# FPGA2_PWR.net
KiCad netlist of a schematic drawn in Altium Designer
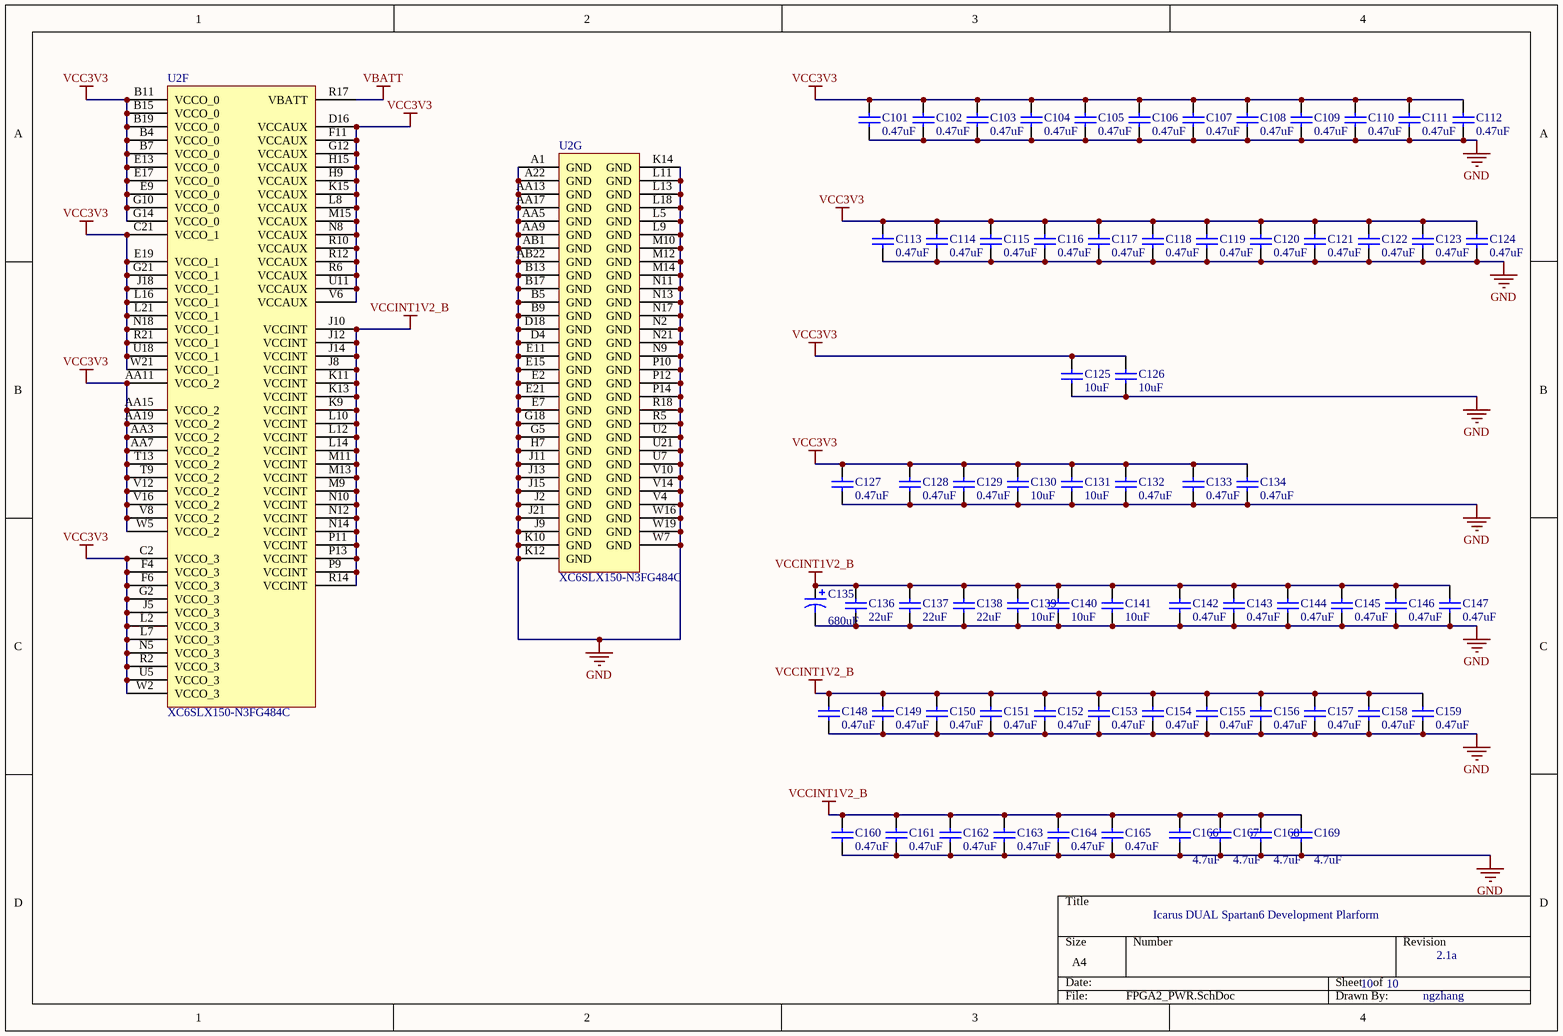
[diagram p0: FPGA2_PWR.SchDoc]

(export (version "E")
  (design (tool "Eeschema 10.0.6"))
  (components
    (comp (ref "C101")
      (value "0.47uF")
      (footprint "BGA0402")
      (description "Capacitor (Semiconductor SIM Model)")
      (fields (field (name "PUBLISHER") "Altium Limited"))
      (libsource (lib "Miscellaneous Devices") (part "Cap Semi"))
    )
    (comp (ref "C102")
      (value "0.47uF")
      (footprint "BGA0402")
      (description "Capacitor (Semiconductor SIM Model)")
      (fields (field (name "PUBLISHER") "Altium Limited"))
      (libsource (lib "Miscellaneous Devices") (part "Cap Semi"))
    )
    (comp (ref "C103")
      (value "0.47uF")
      (footprint "BGA0402")
      (description "Capacitor (Semiconductor SIM Model)")
      (fields (field (name "PUBLISHER") "Altium Limited"))
      (libsource (lib "Miscellaneous Devices") (part "Cap Semi"))
    )
    (comp (ref "C104")
      (value "0.47uF")
      (footprint "BGA0402")
      (description "Capacitor (Semiconductor SIM Model)")
      (fields (field (name "PUBLISHER") "Altium Limited"))
      (libsource (lib "Miscellaneous Devices") (part "Cap Semi"))
    )
    (comp (ref "C105")
      (value "0.47uF")
      (footprint "BGA0402")
      (description "Capacitor (Semiconductor SIM Model)")
      (fields (field (name "PUBLISHER") "Altium Limited"))
      (libsource (lib "Miscellaneous Devices") (part "Cap Semi"))
    )
    (comp (ref "C106")
      (value "0.47uF")
      (footprint "BGA0402")
      (description "Capacitor (Semiconductor SIM Model)")
      (fields (field (name "PUBLISHER") "Altium Limited"))
      (libsource (lib "Miscellaneous Devices") (part "Cap Semi"))
    )
    (comp (ref "C107")
      (value "0.47uF")
      (footprint "BGA0402")
      (description "Capacitor (Semiconductor SIM Model)")
      (fields (field (name "PUBLISHER") "Altium Limited"))
      (libsource (lib "Miscellaneous Devices") (part "Cap Semi"))
    )
    (comp (ref "C108")
      (value "0.47uF")
      (footprint "BGA0402")
      (description "Capacitor (Semiconductor SIM Model)")
      (fields (field (name "PUBLISHER") "Altium Limited"))
      (libsource (lib "Miscellaneous Devices") (part "Cap Semi"))
    )
    (comp (ref "C109")
      (value "0.47uF")
      (footprint "BGA0402")
      (description "Capacitor (Semiconductor SIM Model)")
      (fields (field (name "PUBLISHER") "Altium Limited"))
      (libsource (lib "Miscellaneous Devices") (part "Cap Semi"))
    )
    (comp (ref "C110")
      (value "0.47uF")
      (footprint "BGA0402")
      (description "Capacitor (Semiconductor SIM Model)")
      (fields (field (name "PUBLISHER") "Altium Limited"))
      (libsource (lib "Miscellaneous Devices") (part "Cap Semi"))
    )
    (comp (ref "C111")
      (value "0.47uF")
      (footprint "BGA0402")
      (description "Capacitor (Semiconductor SIM Model)")
      (fields (field (name "PUBLISHER") "Altium Limited"))
      (libsource (lib "Miscellaneous Devices") (part "Cap Semi"))
    )
    (comp (ref "C112")
      (value "0.47uF")
      (footprint "BGA0402")
      (description "Capacitor (Semiconductor SIM Model)")
      (fields (field (name "PUBLISHER") "Altium Limited"))
      (libsource (lib "Miscellaneous Devices") (part "Cap Semi"))
    )
    (comp (ref "C113")
      (value "0.47uF")
      (footprint "BGA0402")
      (description "Capacitor (Semiconductor SIM Model)")
      (fields (field (name "PUBLISHER") "Altium Limited"))
      (libsource (lib "Miscellaneous Devices") (part "Cap Semi"))
    )
    (comp (ref "C114")
      (value "0.47uF")
      (footprint "BGA0402")
      (description "Capacitor (Semiconductor SIM Model)")
      (fields (field (name "PUBLISHER") "Altium Limited"))
      (libsource (lib "Miscellaneous Devices") (part "Cap Semi"))
    )
    (comp (ref "C115")
      (value "0.47uF")
      (footprint "BGA0402")
      (description "Capacitor (Semiconductor SIM Model)")
      (fields (field (name "PUBLISHER") "Altium Limited"))
      (libsource (lib "Miscellaneous Devices") (part "Cap Semi"))
    )
    (comp (ref "C116")
      (value "0.47uF")
      (footprint "BGA0402")
      (description "Capacitor (Semiconductor SIM Model)")
      (fields (field (name "PUBLISHER") "Altium Limited"))
      (libsource (lib "Miscellaneous Devices") (part "Cap Semi"))
    )
    (comp (ref "C117")
      (value "0.47uF")
      (footprint "BGA0402")
      (description "Capacitor (Semiconductor SIM Model)")
      (fields (field (name "PUBLISHER") "Altium Limited"))
      (libsource (lib "Miscellaneous Devices") (part "Cap Semi"))
    )
    (comp (ref "C118")
      (value "0.47uF")
      (footprint "BGA0402")
      (description "Capacitor (Semiconductor SIM Model)")
      (fields (field (name "PUBLISHER") "Altium Limited"))
      (libsource (lib "Miscellaneous Devices") (part "Cap Semi"))
    )
    (comp (ref "C119")
      (value "0.47uF")
      (footprint "BGA0402")
      (description "Capacitor (Semiconductor SIM Model)")
      (fields (field (name "PUBLISHER") "Altium Limited"))
      (libsource (lib "Miscellaneous Devices") (part "Cap Semi"))
    )
    (comp (ref "C120")
      (value "0.47uF")
      (footprint "BGA0402")
      (description "Capacitor (Semiconductor SIM Model)")
      (fields (field (name "PUBLISHER") "Altium Limited"))
      (libsource (lib "Miscellaneous Devices") (part "Cap Semi"))
    )
    (comp (ref "C121")
      (value "0.47uF")
      (footprint "BGA0402")
      (description "Capacitor (Semiconductor SIM Model)")
      (fields (field (name "PUBLISHER") "Altium Limited"))
      (libsource (lib "Miscellaneous Devices") (part "Cap Semi"))
    )
    (comp (ref "C122")
      (value "0.47uF")
      (footprint "BGA0402")
      (description "Capacitor (Semiconductor SIM Model)")
      (fields (field (name "PUBLISHER") "Altium Limited"))
      (libsource (lib "Miscellaneous Devices") (part "Cap Semi"))
    )
    (comp (ref "C123")
      (value "0.47uF")
      (footprint "BGA0402")
      (description "Capacitor (Semiconductor SIM Model)")
      (fields (field (name "PUBLISHER") "Altium Limited"))
      (libsource (lib "Miscellaneous Devices") (part "Cap Semi"))
    )
    (comp (ref "C124")
      (value "0.47uF")
      (footprint "BGA0402")
      (description "Capacitor (Semiconductor SIM Model)")
      (fields (field (name "PUBLISHER") "Altium Limited"))
      (libsource (lib "Miscellaneous Devices") (part "Cap Semi"))
    )
    (comp (ref "C125")
      (value "10uF")
      (footprint "CAPC2012N")
      (description "Capacitor (Semiconductor SIM Model)")
      (fields (field (name "PUBLISHER") "Altium Limited"))
      (libsource (lib "Miscellaneous Devices") (part "Cap Semi"))
    )
    (comp (ref "C126")
      (value "10uF")
      (footprint "CAPC2012N")
      (description "Capacitor (Semiconductor SIM Model)")
      (fields (field (name "PUBLISHER") "Altium Limited"))
      (libsource (lib "Miscellaneous Devices") (part "Cap Semi"))
    )
    (comp (ref "C127")
      (value "0.47uF")
      (footprint "BGA0402")
      (description "Capacitor (Semiconductor SIM Model)")
      (fields (field (name "PUBLISHER") "Altium Limited"))
      (libsource (lib "Miscellaneous Devices") (part "Cap Semi"))
    )
    (comp (ref "C128")
      (value "0.47uF")
      (footprint "BGA0402")
      (description "Capacitor (Semiconductor SIM Model)")
      (fields (field (name "PUBLISHER") "Altium Limited"))
      (libsource (lib "Miscellaneous Devices") (part "Cap Semi"))
    )
    (comp (ref "C129")
      (value "0.47uF")
      (footprint "BGA0402")
      (description "Capacitor (Semiconductor SIM Model)")
      (fields (field (name "PUBLISHER") "Altium Limited"))
      (libsource (lib "Miscellaneous Devices") (part "Cap Semi"))
    )
    (comp (ref "C130")
      (value "10uF")
      (footprint "CAPC2012N")
      (description "Capacitor (Semiconductor SIM Model)")
      (fields (field (name "PUBLISHER") "Altium Limited"))
      (libsource (lib "Miscellaneous Devices") (part "Cap Semi"))
    )
    (comp (ref "C131")
      (value "10uF")
      (footprint "CAPC2012N")
      (description "Capacitor (Semiconductor SIM Model)")
      (fields (field (name "PUBLISHER") "Altium Limited"))
      (libsource (lib "Miscellaneous Devices") (part "Cap Semi"))
    )
    (comp (ref "C132")
      (value "0.47uF")
      (footprint "BGA0402")
      (description "Capacitor (Semiconductor SIM Model)")
      (fields (field (name "PUBLISHER") "Altium Limited"))
      (libsource (lib "Miscellaneous Devices") (part "Cap Semi"))
    )
    (comp (ref "C133")
      (value "0.47uF")
      (footprint "BGA0402")
      (description "Capacitor (Semiconductor SIM Model)")
      (fields (field (name "PUBLISHER") "Altium Limited"))
      (libsource (lib "Miscellaneous Devices") (part "Cap Semi"))
    )
    (comp (ref "C134")
      (value "0.47uF")
      (footprint "BGA0402")
      (description "Capacitor (Semiconductor SIM Model)")
      (fields (field (name "PUBLISHER") "Altium Limited"))
      (libsource (lib "Miscellaneous Devices") (part "Cap Semi"))
    )
    (comp (ref "C135")
      (value "680uF")
      (footprint "D")
      (description "Polarized Capacitor (Surface Mount)")
      (fields (field (name "PUBLISHER") "Altium Limited"))
      (libsource (lib "Miscellaneous Devices") (part "Cap Pol3"))
    )
    (comp (ref "C136")
      (value "22uF")
      (footprint "CAPC3216N")
      (description "Capacitor (Semiconductor SIM Model)")
      (fields (field (name "PUBLISHER") "Altium Limited"))
      (libsource (lib "Miscellaneous Devices") (part "Cap Semi"))
    )
    (comp (ref "C137")
      (value "22uF")
      (footprint "CAPC3216N")
      (description "Capacitor (Semiconductor SIM Model)")
      (fields (field (name "PUBLISHER") "Altium Limited"))
      (libsource (lib "Miscellaneous Devices") (part "Cap Semi"))
    )
    (comp (ref "C138")
      (value "22uF")
      (footprint "CAPC3216N")
      (description "Capacitor (Semiconductor SIM Model)")
      (fields (field (name "PUBLISHER") "Altium Limited"))
      (libsource (lib "Miscellaneous Devices") (part "Cap Semi"))
    )
    (comp (ref "C139")
      (value "10uF")
      (footprint "CAPC2012N")
      (description "Capacitor (Semiconductor SIM Model)")
      (fields (field (name "PUBLISHER") "Altium Limited"))
      (libsource (lib "Miscellaneous Devices") (part "Cap Semi"))
    )
    (comp (ref "C140")
      (value "10uF")
      (footprint "CAPC2012N")
      (description "Capacitor (Semiconductor SIM Model)")
      (fields (field (name "PUBLISHER") "Altium Limited"))
      (libsource (lib "Miscellaneous Devices") (part "Cap Semi"))
    )
    (comp (ref "C141")
      (value "10uF")
      (footprint "CAPC2012N")
      (description "Capacitor (Semiconductor SIM Model)")
      (fields (field (name "PUBLISHER") "Altium Limited"))
      (libsource (lib "Miscellaneous Devices") (part "Cap Semi"))
    )
    (comp (ref "C142")
      (value "0.47uF")
      (footprint "BGA0402")
      (description "Capacitor (Semiconductor SIM Model)")
      (fields (field (name "PUBLISHER") "Altium Limited"))
      (libsource (lib "Miscellaneous Devices") (part "Cap Semi"))
    )
    (comp (ref "C143")
      (value "0.47uF")
      (footprint "BGA0402")
      (description "Capacitor (Semiconductor SIM Model)")
      (fields (field (name "PUBLISHER") "Altium Limited"))
      (libsource (lib "Miscellaneous Devices") (part "Cap Semi"))
    )
    (comp (ref "C144")
      (value "0.47uF")
      (footprint "BGA0402")
      (description "Capacitor (Semiconductor SIM Model)")
      (fields (field (name "PUBLISHER") "Altium Limited"))
      (libsource (lib "Miscellaneous Devices") (part "Cap Semi"))
    )
    (comp (ref "C145")
      (value "0.47uF")
      (footprint "BGA0402")
      (description "Capacitor (Semiconductor SIM Model)")
      (fields (field (name "PUBLISHER") "Altium Limited"))
      (libsource (lib "Miscellaneous Devices") (part "Cap Semi"))
    )
    (comp (ref "C146")
      (value "0.47uF")
      (footprint "BGA0402")
      (description "Capacitor (Semiconductor SIM Model)")
      (fields (field (name "PUBLISHER") "Altium Limited"))
      (libsource (lib "Miscellaneous Devices") (part "Cap Semi"))
    )
    (comp (ref "C147")
      (value "0.47uF")
      (footprint "BGA0402")
      (description "Capacitor (Semiconductor SIM Model)")
      (fields (field (name "PUBLISHER") "Altium Limited"))
      (libsource (lib "Miscellaneous Devices") (part "Cap Semi"))
    )
    (comp (ref "C148")
      (value "0.47uF")
      (footprint "BGA0402")
      (description "Capacitor (Semiconductor SIM Model)")
      (fields (field (name "PUBLISHER") "Altium Limited"))
      (libsource (lib "Miscellaneous Devices") (part "Cap Semi"))
    )
    (comp (ref "C149")
      (value "0.47uF")
      (footprint "BGA0402")
      (description "Capacitor (Semiconductor SIM Model)")
      (fields (field (name "PUBLISHER") "Altium Limited"))
      (libsource (lib "Miscellaneous Devices") (part "Cap Semi"))
    )
    (comp (ref "C150")
      (value "0.47uF")
      (footprint "BGA0402")
      (description "Capacitor (Semiconductor SIM Model)")
      (fields (field (name "PUBLISHER") "Altium Limited"))
      (libsource (lib "Miscellaneous Devices") (part "Cap Semi"))
    )
    (comp (ref "C151")
      (value "0.47uF")
      (footprint "BGA0402")
      (description "Capacitor (Semiconductor SIM Model)")
      (fields (field (name "PUBLISHER") "Altium Limited"))
      (libsource (lib "Miscellaneous Devices") (part "Cap Semi"))
    )
    (comp (ref "C152")
      (value "0.47uF")
      (footprint "BGA0402")
      (description "Capacitor (Semiconductor SIM Model)")
      (fields (field (name "PUBLISHER") "Altium Limited"))
      (libsource (lib "Miscellaneous Devices") (part "Cap Semi"))
    )
    (comp (ref "C153")
      (value "0.47uF")
      (footprint "BGA0402")
      (description "Capacitor (Semiconductor SIM Model)")
      (fields (field (name "PUBLISHER") "Altium Limited"))
      (libsource (lib "Miscellaneous Devices") (part "Cap Semi"))
    )
    (comp (ref "C154")
      (value "0.47uF")
      (footprint "BGA0402")
      (description "Capacitor (Semiconductor SIM Model)")
      (fields (field (name "PUBLISHER") "Altium Limited"))
      (libsource (lib "Miscellaneous Devices") (part "Cap Semi"))
    )
    (comp (ref "C155")
      (value "0.47uF")
      (footprint "BGA0402")
      (description "Capacitor (Semiconductor SIM Model)")
      (fields (field (name "PUBLISHER") "Altium Limited"))
      (libsource (lib "Miscellaneous Devices") (part "Cap Semi"))
    )
    (comp (ref "C156")
      (value "0.47uF")
      (footprint "BGA0402")
      (description "Capacitor (Semiconductor SIM Model)")
      (fields (field (name "PUBLISHER") "Altium Limited"))
      (libsource (lib "Miscellaneous Devices") (part "Cap Semi"))
    )
    (comp (ref "C157")
      (value "0.47uF")
      (footprint "BGA0402")
      (description "Capacitor (Semiconductor SIM Model)")
      (fields (field (name "PUBLISHER") "Altium Limited"))
      (libsource (lib "Miscellaneous Devices") (part "Cap Semi"))
    )
    (comp (ref "C158")
      (value "0.47uF")
      (footprint "BGA0402")
      (description "Capacitor (Semiconductor SIM Model)")
      (fields (field (name "PUBLISHER") "Altium Limited"))
      (libsource (lib "Miscellaneous Devices") (part "Cap Semi"))
    )
    (comp (ref "C159")
      (value "0.47uF")
      (footprint "BGA0402")
      (description "Capacitor (Semiconductor SIM Model)")
      (fields (field (name "PUBLISHER") "Altium Limited"))
      (libsource (lib "Miscellaneous Devices") (part "Cap Semi"))
    )
    (comp (ref "C160")
      (value "0.47uF")
      (footprint "BGA0402")
      (description "Capacitor (Semiconductor SIM Model)")
      (fields (field (name "PUBLISHER") "Altium Limited"))
      (libsource (lib "Miscellaneous Devices") (part "Cap Semi"))
    )
    (comp (ref "C161")
      (value "0.47uF")
      (footprint "BGA0402")
      (description "Capacitor (Semiconductor SIM Model)")
      (fields (field (name "PUBLISHER") "Altium Limited"))
      (libsource (lib "Miscellaneous Devices") (part "Cap Semi"))
    )
    (comp (ref "C162")
      (value "0.47uF")
      (footprint "BGA0402")
      (description "Capacitor (Semiconductor SIM Model)")
      (fields (field (name "PUBLISHER") "Altium Limited"))
      (libsource (lib "Miscellaneous Devices") (part "Cap Semi"))
    )
    (comp (ref "C163")
      (value "0.47uF")
      (footprint "BGA0402")
      (description "Capacitor (Semiconductor SIM Model)")
      (fields (field (name "PUBLISHER") "Altium Limited"))
      (libsource (lib "Miscellaneous Devices") (part "Cap Semi"))
    )
    (comp (ref "C164")
      (value "0.47uF")
      (footprint "BGA0402")
      (description "Capacitor (Semiconductor SIM Model)")
      (fields (field (name "PUBLISHER") "Altium Limited"))
      (libsource (lib "Miscellaneous Devices") (part "Cap Semi"))
    )
    (comp (ref "C165")
      (value "0.47uF")
      (footprint "BGA0402")
      (description "Capacitor (Semiconductor SIM Model)")
      (fields (field (name "PUBLISHER") "Altium Limited"))
      (libsource (lib "Miscellaneous Devices") (part "Cap Semi"))
    )
    (comp (ref "C166")
      (value "4.7uF")
      (footprint "CAPC1608N")
      (description "Capacitor (Semiconductor SIM Model)")
      (fields (field (name "PUBLISHER") "Altium Limited"))
      (libsource (lib "Miscellaneous Devices") (part "Cap Semi"))
    )
    (comp (ref "C167")
      (value "4.7uF")
      (footprint "CAPC1608N")
      (description "Capacitor (Semiconductor SIM Model)")
      (fields (field (name "PUBLISHER") "Altium Limited"))
      (libsource (lib "Miscellaneous Devices") (part "Cap Semi"))
    )
    (comp (ref "C168")
      (value "4.7uF")
      (footprint "CAPC1608N")
      (description "Capacitor (Semiconductor SIM Model)")
      (fields (field (name "PUBLISHER") "Altium Limited"))
      (libsource (lib "Miscellaneous Devices") (part "Cap Semi"))
    )
    (comp (ref "C169")
      (value "4.7uF")
      (footprint "CAPC1608N")
      (description "Capacitor (Semiconductor SIM Model)")
      (fields (field (name "PUBLISHER") "Altium Limited"))
      (libsource (lib "Miscellaneous Devices") (part "Cap Semi"))
    )
    (comp (ref "U2")
      (value "XC6SLX150-N3FG484C")
      (footprint "FG484")
      (fields (field (name "PUBLISHER") "Altium Limited"))
      (libsource (lib "Xilinx Spartan-6") (part "XC6SLX150-N3FG484C"))
    )
  )
  (nets
    (net (code "1") (name "GND") (class "Default")
      (node (ref "C101") (pin "1") (pinfunction "1_1") (pintype "passive"))
      (node (ref "C102") (pin "1") (pinfunction "1_1") (pintype "passive"))
      (node (ref "C103") (pin "1") (pinfunction "1_1") (pintype "passive"))
      (node (ref "C104") (pin "1") (pinfunction "1_1") (pintype "passive"))
      (node (ref "C105") (pin "1") (pinfunction "1_1") (pintype "passive"))
      (node (ref "C106") (pin "1") (pinfunction "1_1") (pintype "passive"))
      (node (ref "C107") (pin "1") (pinfunction "1_1") (pintype "passive"))
      (node (ref "C108") (pin "1") (pinfunction "1_1") (pintype "passive"))
      (node (ref "C109") (pin "1") (pinfunction "1_1") (pintype "passive"))
      (node (ref "C110") (pin "1") (pinfunction "1_1") (pintype "passive"))
      (node (ref "C111") (pin "1") (pinfunction "1_1") (pintype "passive"))
      (node (ref "C112") (pin "1") (pinfunction "1_1") (pintype "passive"))
      (node (ref "C113") (pin "1") (pinfunction "1_1") (pintype "passive"))
      (node (ref "C114") (pin "1") (pinfunction "1_1") (pintype "passive"))
      (node (ref "C115") (pin "1") (pinfunction "1_1") (pintype "passive"))
      (node (ref "C116") (pin "1") (pinfunction "1_1") (pintype "passive"))
      (node (ref "C117") (pin "1") (pinfunction "1_1") (pintype "passive"))
      (node (ref "C118") (pin "1") (pinfunction "1_1") (pintype "passive"))
      (node (ref "C119") (pin "1") (pinfunction "1_1") (pintype "passive"))
      (node (ref "C120") (pin "1") (pinfunction "1_1") (pintype "passive"))
      (node (ref "C121") (pin "1") (pinfunction "1_1") (pintype "passive"))
      (node (ref "C122") (pin "1") (pinfunction "1_1") (pintype "passive"))
      (node (ref "C123") (pin "1") (pinfunction "1_1") (pintype "passive"))
      (node (ref "C124") (pin "1") (pinfunction "1_1") (pintype "passive"))
      (node (ref "C125") (pin "1") (pinfunction "1_1") (pintype "passive"))
      (node (ref "C126") (pin "1") (pinfunction "1_1") (pintype "passive"))
      (node (ref "C127") (pin "1") (pinfunction "1_1") (pintype "passive"))
      (node (ref "C128") (pin "1") (pinfunction "1_1") (pintype "passive"))
      (node (ref "C129") (pin "1") (pinfunction "1_1") (pintype "passive"))
      (node (ref "C130") (pin "1") (pinfunction "1_1") (pintype "passive"))
      (node (ref "C131") (pin "1") (pinfunction "1_1") (pintype "passive"))
      (node (ref "C132") (pin "1") (pinfunction "1_1") (pintype "passive"))
      (node (ref "C133") (pin "1") (pinfunction "1_1") (pintype "passive"))
      (node (ref "C134") (pin "1") (pinfunction "1_1") (pintype "passive"))
      (node (ref "C135") (pin "2") (pinfunction "2_2") (pintype "passive"))
      (node (ref "C136") (pin "1") (pinfunction "1_1") (pintype "passive"))
      (node (ref "C137") (pin "1") (pinfunction "1_1") (pintype "passive"))
      (node (ref "C138") (pin "1") (pinfunction "1_1") (pintype "passive"))
      (node (ref "C139") (pin "1") (pinfunction "1_1") (pintype "passive"))
      (node (ref "C140") (pin "1") (pinfunction "1_1") (pintype "passive"))
      (node (ref "C141") (pin "1") (pinfunction "1_1") (pintype "passive"))
      (node (ref "C142") (pin "1") (pinfunction "1_1") (pintype "passive"))
      (node (ref "C143") (pin "1") (pinfunction "1_1") (pintype "passive"))
      (node (ref "C144") (pin "1") (pinfunction "1_1") (pintype "passive"))
      (node (ref "C145") (pin "1") (pinfunction "1_1") (pintype "passive"))
      (node (ref "C146") (pin "1") (pinfunction "1_1") (pintype "passive"))
      (node (ref "C147") (pin "1") (pinfunction "1_1") (pintype "passive"))
      (node (ref "C148") (pin "1") (pinfunction "1_1") (pintype "passive"))
      (node (ref "C149") (pin "1") (pinfunction "1_1") (pintype "passive"))
      (node (ref "C150") (pin "1") (pinfunction "1_1") (pintype "passive"))
      (node (ref "C151") (pin "1") (pinfunction "1_1") (pintype "passive"))
      (node (ref "C152") (pin "1") (pinfunction "1_1") (pintype "passive"))
      (node (ref "C153") (pin "1") (pinfunction "1_1") (pintype "passive"))
      (node (ref "C154") (pin "1") (pinfunction "1_1") (pintype "passive"))
      (node (ref "C155") (pin "1") (pinfunction "1_1") (pintype "passive"))
      (node (ref "C156") (pin "1") (pinfunction "1_1") (pintype "passive"))
      (node (ref "C157") (pin "1") (pinfunction "1_1") (pintype "passive"))
      (node (ref "C158") (pin "1") (pinfunction "1_1") (pintype "passive"))
      (node (ref "C159") (pin "1") (pinfunction "1_1") (pintype "passive"))
      (node (ref "C160") (pin "1") (pinfunction "1_1") (pintype "passive"))
      (node (ref "C161") (pin "1") (pinfunction "1_1") (pintype "passive"))
      (node (ref "C162") (pin "1") (pinfunction "1_1") (pintype "passive"))
      (node (ref "C163") (pin "1") (pinfunction "1_1") (pintype "passive"))
      (node (ref "C164") (pin "1") (pinfunction "1_1") (pintype "passive"))
      (node (ref "C165") (pin "1") (pinfunction "1_1") (pintype "passive"))
      (node (ref "C166") (pin "1") (pinfunction "1_1") (pintype "passive"))
      (node (ref "C167") (pin "1") (pinfunction "1_1") (pintype "passive"))
      (node (ref "C168") (pin "1") (pinfunction "1_1") (pintype "passive"))
      (node (ref "C169") (pin "1") (pinfunction "1_1") (pintype "passive"))
      (node (ref "U2") (pin "A1") (pinfunction "GND_A1") (pintype "power_in"))
      (node (ref "U2") (pin "A22") (pinfunction "GND_A22") (pintype "power_in"))
      (node (ref "U2") (pin "AA13") (pinfunction "GND_AA13") (pintype "power_in"))
      (node (ref "U2") (pin "AA17") (pinfunction "GND_AA17") (pintype "power_in"))
      (node (ref "U2") (pin "AA5") (pinfunction "GND_AA5") (pintype "power_in"))
      (node (ref "U2") (pin "AA9") (pinfunction "GND_AA9") (pintype "power_in"))
      (node (ref "U2") (pin "AB1") (pinfunction "GND_AB1") (pintype "power_in"))
      (node (ref "U2") (pin "AB22") (pinfunction "GND_AB22") (pintype "power_in"))
      (node (ref "U2") (pin "B13") (pinfunction "GND_B13") (pintype "power_in"))
      (node (ref "U2") (pin "B17") (pinfunction "GND_B17") (pintype "power_in"))
      (node (ref "U2") (pin "B5") (pinfunction "GND_B5") (pintype "power_in"))
      (node (ref "U2") (pin "B9") (pinfunction "GND_B9") (pintype "power_in"))
      (node (ref "U2") (pin "D18") (pinfunction "GND_D18") (pintype "power_in"))
      (node (ref "U2") (pin "D4") (pinfunction "GND_D4") (pintype "power_in"))
      (node (ref "U2") (pin "E11") (pinfunction "GND_E11") (pintype "power_in"))
      (node (ref "U2") (pin "E15") (pinfunction "GND_E15") (pintype "power_in"))
      (node (ref "U2") (pin "E2") (pinfunction "GND_E2") (pintype "power_in"))
      (node (ref "U2") (pin "E21") (pinfunction "GND_E21") (pintype "power_in"))
      (node (ref "U2") (pin "E7") (pinfunction "GND_E7") (pintype "power_in"))
      (node (ref "U2") (pin "G18") (pinfunction "GND_G18") (pintype "power_in"))
      (node (ref "U2") (pin "G5") (pinfunction "GND_G5") (pintype "power_in"))
      (node (ref "U2") (pin "H7") (pinfunction "GND_H7") (pintype "power_in"))
      (node (ref "U2") (pin "J11") (pinfunction "GND_J11") (pintype "power_in"))
      (node (ref "U2") (pin "J13") (pinfunction "GND_J13") (pintype "power_in"))
      (node (ref "U2") (pin "J15") (pinfunction "GND_J15") (pintype "power_in"))
      (node (ref "U2") (pin "J2") (pinfunction "GND_J2") (pintype "power_in"))
      (node (ref "U2") (pin "J21") (pinfunction "GND_J21") (pintype "power_in"))
      (node (ref "U2") (pin "J9") (pinfunction "GND_J9") (pintype "power_in"))
      (node (ref "U2") (pin "K10") (pinfunction "GND_K10") (pintype "power_in"))
      (node (ref "U2") (pin "K12") (pinfunction "GND_K12") (pintype "power_in"))
      (node (ref "U2") (pin "K14") (pinfunction "GND_K14") (pintype "power_in"))
      (node (ref "U2") (pin "L11") (pinfunction "GND_L11") (pintype "power_in"))
      (node (ref "U2") (pin "L13") (pinfunction "GND_L13") (pintype "power_in"))
      (node (ref "U2") (pin "L18") (pinfunction "GND_L18") (pintype "power_in"))
      (node (ref "U2") (pin "L5") (pinfunction "GND_L5") (pintype "power_in"))
      (node (ref "U2") (pin "L9") (pinfunction "GND_L9") (pintype "power_in"))
      (node (ref "U2") (pin "M10") (pinfunction "GND_M10") (pintype "power_in"))
      (node (ref "U2") (pin "M12") (pinfunction "GND_M12") (pintype "power_in"))
      (node (ref "U2") (pin "M14") (pinfunction "GND_M14") (pintype "power_in"))
      (node (ref "U2") (pin "N11") (pinfunction "GND_N11") (pintype "power_in"))
      (node (ref "U2") (pin "N13") (pinfunction "GND_N13") (pintype "power_in"))
      (node (ref "U2") (pin "N17") (pinfunction "GND_N17") (pintype "power_in"))
      (node (ref "U2") (pin "N2") (pinfunction "GND_N2") (pintype "power_in"))
      (node (ref "U2") (pin "N21") (pinfunction "GND_N21") (pintype "power_in"))
      (node (ref "U2") (pin "N9") (pinfunction "GND_N9") (pintype "power_in"))
      (node (ref "U2") (pin "P10") (pinfunction "GND_P10") (pintype "power_in"))
      (node (ref "U2") (pin "P12") (pinfunction "GND_P12") (pintype "power_in"))
      (node (ref "U2") (pin "P14") (pinfunction "GND_P14") (pintype "power_in"))
      (node (ref "U2") (pin "R18") (pinfunction "GND_R18") (pintype "power_in"))
      (node (ref "U2") (pin "R5") (pinfunction "GND_R5") (pintype "power_in"))
      (node (ref "U2") (pin "U2") (pinfunction "GND_U2") (pintype "power_in"))
      (node (ref "U2") (pin "U21") (pinfunction "GND_U21") (pintype "power_in"))
      (node (ref "U2") (pin "U7") (pinfunction "GND_U7") (pintype "power_in"))
      (node (ref "U2") (pin "V10") (pinfunction "GND_V10") (pintype "power_in"))
      (node (ref "U2") (pin "V14") (pinfunction "GND_V14") (pintype "power_in"))
      (node (ref "U2") (pin "V4") (pinfunction "GND_V4") (pintype "power_in"))
      (node (ref "U2") (pin "W16") (pinfunction "GND_W16") (pintype "power_in"))
      (node (ref "U2") (pin "W19") (pinfunction "GND_W19") (pintype "power_in"))
      (node (ref "U2") (pin "W7") (pinfunction "GND_W7") (pintype "power_in"))
    )
    (net (code "2") (name "VBATT") (class "Default")
      (node (ref "U2") (pin "R17") (pinfunction "VBATT_R17") (pintype "power_in"))
    )
    (net (code "3") (name "VCC3V3") (class "Default")
      (node (ref "C101") (pin "2") (pinfunction "2_2") (pintype "passive"))
      (node (ref "C102") (pin "2") (pinfunction "2_2") (pintype "passive"))
      (node (ref "C103") (pin "2") (pinfunction "2_2") (pintype "passive"))
      (node (ref "C104") (pin "2") (pinfunction "2_2") (pintype "passive"))
      (node (ref "C105") (pin "2") (pinfunction "2_2") (pintype "passive"))
      (node (ref "C106") (pin "2") (pinfunction "2_2") (pintype "passive"))
      (node (ref "C107") (pin "2") (pinfunction "2_2") (pintype "passive"))
      (node (ref "C108") (pin "2") (pinfunction "2_2") (pintype "passive"))
      (node (ref "C109") (pin "2") (pinfunction "2_2") (pintype "passive"))
      (node (ref "C110") (pin "2") (pinfunction "2_2") (pintype "passive"))
      (node (ref "C111") (pin "2") (pinfunction "2_2") (pintype "passive"))
      (node (ref "C112") (pin "2") (pinfunction "2_2") (pintype "passive"))
      (node (ref "C113") (pin "2") (pinfunction "2_2") (pintype "passive"))
      (node (ref "C114") (pin "2") (pinfunction "2_2") (pintype "passive"))
      (node (ref "C115") (pin "2") (pinfunction "2_2") (pintype "passive"))
      (node (ref "C116") (pin "2") (pinfunction "2_2") (pintype "passive"))
      (node (ref "C117") (pin "2") (pinfunction "2_2") (pintype "passive"))
      (node (ref "C118") (pin "2") (pinfunction "2_2") (pintype "passive"))
      (node (ref "C119") (pin "2") (pinfunction "2_2") (pintype "passive"))
      (node (ref "C120") (pin "2") (pinfunction "2_2") (pintype "passive"))
      (node (ref "C121") (pin "2") (pinfunction "2_2") (pintype "passive"))
      (node (ref "C122") (pin "2") (pinfunction "2_2") (pintype "passive"))
      (node (ref "C123") (pin "2") (pinfunction "2_2") (pintype "passive"))
      (node (ref "C124") (pin "2") (pinfunction "2_2") (pintype "passive"))
      (node (ref "C125") (pin "2") (pinfunction "2_2") (pintype "passive"))
      (node (ref "C126") (pin "2") (pinfunction "2_2") (pintype "passive"))
      (node (ref "C127") (pin "2") (pinfunction "2_2") (pintype "passive"))
      (node (ref "C128") (pin "2") (pinfunction "2_2") (pintype "passive"))
      (node (ref "C129") (pin "2") (pinfunction "2_2") (pintype "passive"))
      (node (ref "C130") (pin "2") (pinfunction "2_2") (pintype "passive"))
      (node (ref "C131") (pin "2") (pinfunction "2_2") (pintype "passive"))
      (node (ref "C132") (pin "2") (pinfunction "2_2") (pintype "passive"))
      (node (ref "C133") (pin "2") (pinfunction "2_2") (pintype "passive"))
      (node (ref "C134") (pin "2") (pinfunction "2_2") (pintype "passive"))
      (node (ref "U2") (pin "AA11") (pinfunction "VCCO_2_AA11") (pintype "power_in"))
      (node (ref "U2") (pin "AA15") (pinfunction "VCCO_2_AA15") (pintype "power_in"))
      (node (ref "U2") (pin "AA19") (pinfunction "VCCO_2_AA19") (pintype "power_in"))
      (node (ref "U2") (pin "AA3") (pinfunction "VCCO_2_AA3") (pintype "power_in"))
      (node (ref "U2") (pin "AA7") (pinfunction "VCCO_2_AA7") (pintype "power_in"))
      (node (ref "U2") (pin "B11") (pinfunction "VCCO_0_B11") (pintype "power_in"))
      (node (ref "U2") (pin "B15") (pinfunction "VCCO_0_B15") (pintype "power_in"))
      (node (ref "U2") (pin "B19") (pinfunction "VCCO_0_B19") (pintype "power_in"))
      (node (ref "U2") (pin "B4") (pinfunction "VCCO_0_B4") (pintype "power_in"))
      (node (ref "U2") (pin "B7") (pinfunction "VCCO_0_B7") (pintype "power_in"))
      (node (ref "U2") (pin "C2") (pinfunction "VCCO_3_C2") (pintype "power_in"))
      (node (ref "U2") (pin "C21") (pinfunction "VCCO_1_C21") (pintype "power_in"))
      (node (ref "U2") (pin "D16") (pinfunction "VCCAUX_D16") (pintype "power_in"))
      (node (ref "U2") (pin "E13") (pinfunction "VCCO_0_E13") (pintype "power_in"))
      (node (ref "U2") (pin "E17") (pinfunction "VCCO_0_E17") (pintype "power_in"))
      (node (ref "U2") (pin "E19") (pinfunction "VCCO_1_E19") (pintype "power_in"))
      (node (ref "U2") (pin "E9") (pinfunction "VCCO_0_E9") (pintype "power_in"))
      (node (ref "U2") (pin "F11") (pinfunction "VCCAUX_F11") (pintype "power_in"))
      (node (ref "U2") (pin "F4") (pinfunction "VCCO_3_F4") (pintype "power_in"))
      (node (ref "U2") (pin "F6") (pinfunction "VCCO_3_F6") (pintype "power_in"))
      (node (ref "U2") (pin "G10") (pinfunction "VCCO_0_G10") (pintype "power_in"))
      (node (ref "U2") (pin "G12") (pinfunction "VCCAUX_G12") (pintype "power_in"))
      (node (ref "U2") (pin "G14") (pinfunction "VCCO_0_G14") (pintype "power_in"))
      (node (ref "U2") (pin "G2") (pinfunction "VCCO_3_G2") (pintype "power_in"))
      (node (ref "U2") (pin "G21") (pinfunction "VCCO_1_G21") (pintype "power_in"))
      (node (ref "U2") (pin "H15") (pinfunction "VCCAUX_H15") (pintype "power_in"))
      (node (ref "U2") (pin "H9") (pinfunction "VCCAUX_H9") (pintype "power_in"))
      (node (ref "U2") (pin "J18") (pinfunction "VCCO_1_J18") (pintype "power_in"))
      (node (ref "U2") (pin "J5") (pinfunction "VCCO_3_J5") (pintype "power_in"))
      (node (ref "U2") (pin "K15") (pinfunction "VCCAUX_K15") (pintype "power_in"))
      (node (ref "U2") (pin "L16") (pinfunction "VCCO_1_L16") (pintype "power_in"))
      (node (ref "U2") (pin "L2") (pinfunction "VCCO_3_L2") (pintype "power_in"))
      (node (ref "U2") (pin "L21") (pinfunction "VCCO_1_L21") (pintype "power_in"))
      (node (ref "U2") (pin "L7") (pinfunction "VCCO_3_L7") (pintype "power_in"))
      (node (ref "U2") (pin "L8") (pinfunction "VCCAUX_L8") (pintype "power_in"))
      (node (ref "U2") (pin "M15") (pinfunction "VCCAUX_M15") (pintype "power_in"))
      (node (ref "U2") (pin "N18") (pinfunction "VCCO_1_N18") (pintype "power_in"))
      (node (ref "U2") (pin "N5") (pinfunction "VCCO_3_N5") (pintype "power_in"))
      (node (ref "U2") (pin "N8") (pinfunction "VCCAUX_N8") (pintype "power_in"))
      (node (ref "U2") (pin "R10") (pinfunction "VCCAUX_R10") (pintype "power_in"))
      (node (ref "U2") (pin "R12") (pinfunction "VCCAUX_R12") (pintype "power_in"))
      (node (ref "U2") (pin "R2") (pinfunction "VCCO_3_R2") (pintype "power_in"))
      (node (ref "U2") (pin "R21") (pinfunction "VCCO_1_R21") (pintype "power_in"))
      (node (ref "U2") (pin "R6") (pinfunction "VCCAUX_R6") (pintype "power_in"))
      (node (ref "U2") (pin "T13") (pinfunction "VCCO_2_T13") (pintype "power_in"))
      (node (ref "U2") (pin "T9") (pinfunction "VCCO_2_T9") (pintype "power_in"))
      (node (ref "U2") (pin "U11") (pinfunction "VCCAUX_U11") (pintype "power_in"))
      (node (ref "U2") (pin "U18") (pinfunction "VCCO_1_U18") (pintype "power_in"))
      (node (ref "U2") (pin "U5") (pinfunction "VCCO_3_U5") (pintype "power_in"))
      (node (ref "U2") (pin "V12") (pinfunction "VCCO_2_V12") (pintype "power_in"))
      (node (ref "U2") (pin "V16") (pinfunction "VCCO_2_V16") (pintype "power_in"))
      (node (ref "U2") (pin "V6") (pinfunction "VCCAUX_V6") (pintype "power_in"))
      (node (ref "U2") (pin "V8") (pinfunction "VCCO_2_V8") (pintype "power_in"))
      (node (ref "U2") (pin "W2") (pinfunction "VCCO_3_W2") (pintype "power_in"))
      (node (ref "U2") (pin "W21") (pinfunction "VCCO_1_W21") (pintype "power_in"))
      (node (ref "U2") (pin "W5") (pinfunction "VCCO_2_W5") (pintype "power_in"))
    )
    (net (code "4") (name "VCCINT1V2_B") (class "Default")
      (node (ref "C135") (pin "1") (pinfunction "1_1") (pintype "passive"))
      (node (ref "C136") (pin "2") (pinfunction "2_2") (pintype "passive"))
      (node (ref "C137") (pin "2") (pinfunction "2_2") (pintype "passive"))
      (node (ref "C138") (pin "2") (pinfunction "2_2") (pintype "passive"))
      (node (ref "C139") (pin "2") (pinfunction "2_2") (pintype "passive"))
      (node (ref "C140") (pin "2") (pinfunction "2_2") (pintype "passive"))
      (node (ref "C141") (pin "2") (pinfunction "2_2") (pintype "passive"))
      (node (ref "C142") (pin "2") (pinfunction "2_2") (pintype "passive"))
      (node (ref "C143") (pin "2") (pinfunction "2_2") (pintype "passive"))
      (node (ref "C144") (pin "2") (pinfunction "2_2") (pintype "passive"))
      (node (ref "C145") (pin "2") (pinfunction "2_2") (pintype "passive"))
      (node (ref "C146") (pin "2") (pinfunction "2_2") (pintype "passive"))
      (node (ref "C147") (pin "2") (pinfunction "2_2") (pintype "passive"))
      (node (ref "C148") (pin "2") (pinfunction "2_2") (pintype "passive"))
      (node (ref "C149") (pin "2") (pinfunction "2_2") (pintype "passive"))
      (node (ref "C150") (pin "2") (pinfunction "2_2") (pintype "passive"))
      (node (ref "C151") (pin "2") (pinfunction "2_2") (pintype "passive"))
      (node (ref "C152") (pin "2") (pinfunction "2_2") (pintype "passive"))
      (node (ref "C153") (pin "2") (pinfunction "2_2") (pintype "passive"))
      (node (ref "C154") (pin "2") (pinfunction "2_2") (pintype "passive"))
      (node (ref "C155") (pin "2") (pinfunction "2_2") (pintype "passive"))
      (node (ref "C156") (pin "2") (pinfunction "2_2") (pintype "passive"))
      (node (ref "C157") (pin "2") (pinfunction "2_2") (pintype "passive"))
      (node (ref "C158") (pin "2") (pinfunction "2_2") (pintype "passive"))
      (node (ref "C159") (pin "2") (pinfunction "2_2") (pintype "passive"))
      (node (ref "C160") (pin "2") (pinfunction "2_2") (pintype "passive"))
      (node (ref "C161") (pin "2") (pinfunction "2_2") (pintype "passive"))
      (node (ref "C162") (pin "2") (pinfunction "2_2") (pintype "passive"))
      (node (ref "C163") (pin "2") (pinfunction "2_2") (pintype "passive"))
      (node (ref "C164") (pin "2") (pinfunction "2_2") (pintype "passive"))
      (node (ref "C165") (pin "2") (pinfunction "2_2") (pintype "passive"))
      (node (ref "C166") (pin "2") (pinfunction "2_2") (pintype "passive"))
      (node (ref "C167") (pin "2") (pinfunction "2_2") (pintype "passive"))
      (node (ref "C168") (pin "2") (pinfunction "2_2") (pintype "passive"))
      (node (ref "C169") (pin "2") (pinfunction "2_2") (pintype "passive"))
      (node (ref "U2") (pin "J10") (pinfunction "VCCINT_J10") (pintype "power_in"))
      (node (ref "U2") (pin "J12") (pinfunction "VCCINT_J12") (pintype "power_in"))
      (node (ref "U2") (pin "J14") (pinfunction "VCCINT_J14") (pintype "power_in"))
      (node (ref "U2") (pin "J8") (pinfunction "VCCINT_J8") (pintype "power_in"))
      (node (ref "U2") (pin "K11") (pinfunction "VCCINT_K11") (pintype "power_in"))
      (node (ref "U2") (pin "K13") (pinfunction "VCCINT_K13") (pintype "power_in"))
      (node (ref "U2") (pin "K9") (pinfunction "VCCINT_K9") (pintype "power_in"))
      (node (ref "U2") (pin "L10") (pinfunction "VCCINT_L10") (pintype "power_in"))
      (node (ref "U2") (pin "L12") (pinfunction "VCCINT_L12") (pintype "power_in"))
      (node (ref "U2") (pin "L14") (pinfunction "VCCINT_L14") (pintype "power_in"))
      (node (ref "U2") (pin "M11") (pinfunction "VCCINT_M11") (pintype "power_in"))
      (node (ref "U2") (pin "M13") (pinfunction "VCCINT_M13") (pintype "power_in"))
      (node (ref "U2") (pin "M9") (pinfunction "VCCINT_M9") (pintype "power_in"))
      (node (ref "U2") (pin "N10") (pinfunction "VCCINT_N10") (pintype "power_in"))
      (node (ref "U2") (pin "N12") (pinfunction "VCCINT_N12") (pintype "power_in"))
      (node (ref "U2") (pin "N14") (pinfunction "VCCINT_N14") (pintype "power_in"))
      (node (ref "U2") (pin "P11") (pinfunction "VCCINT_P11") (pintype "power_in"))
      (node (ref "U2") (pin "P13") (pinfunction "VCCINT_P13") (pintype "power_in"))
      (node (ref "U2") (pin "P9") (pinfunction "VCCINT_P9") (pintype "power_in"))
      (node (ref "U2") (pin "R14") (pinfunction "VCCINT_R14") (pintype "power_in"))
    )
  )
)
